# usb_snes.net
KiCad netlist of a schematic drawn in EAGLE
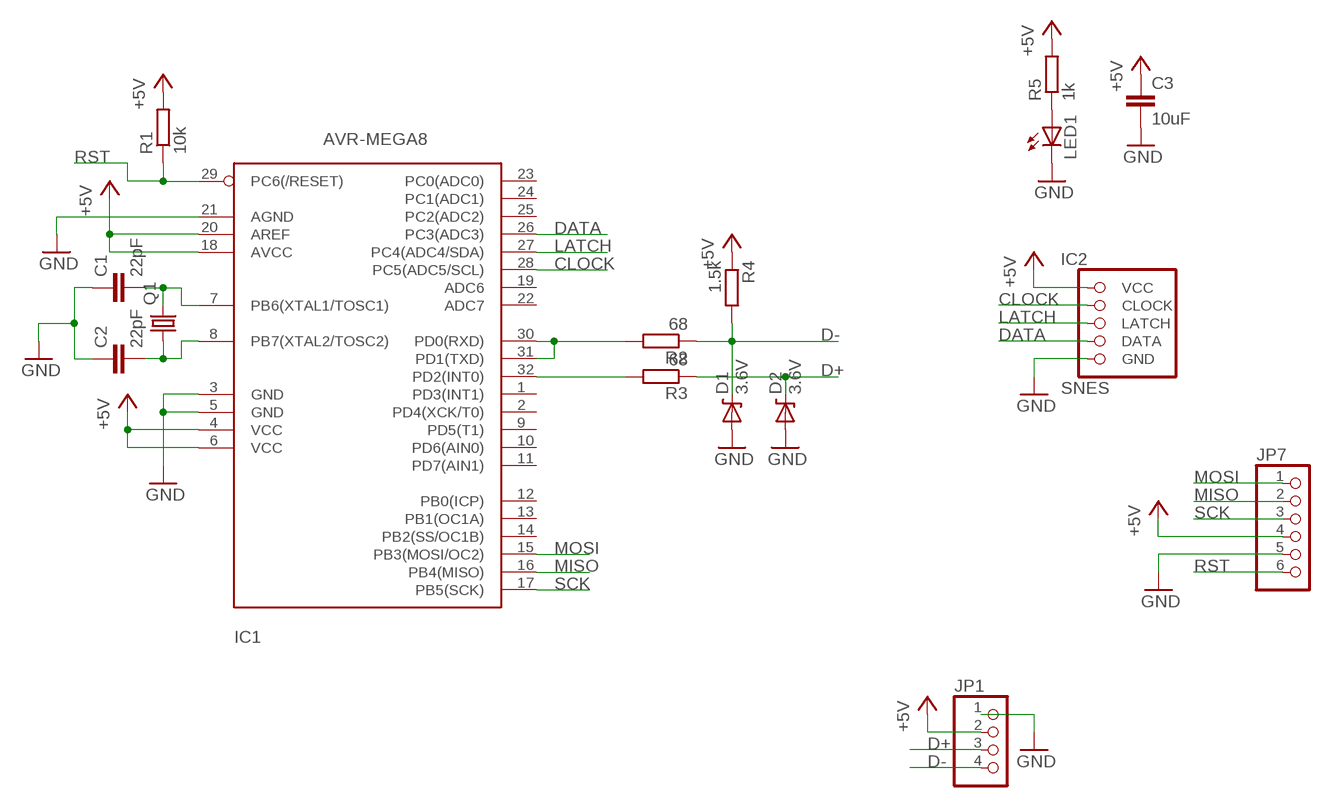
[diagram p0: schematic, sheet 1]

(export (version "E")
  (design (tool "Eeschema 10.0.6"))
  (components
    (comp (ref "C1")
      (value "22pF")
      (footprint "eagle-import:R0805")
      (libsource (lib "eagle-import") (part "C-EUR0805"))
    )
    (comp (ref "C2")
      (value "22pF")
      (footprint "eagle-import:R0805")
      (libsource (lib "eagle-import") (part "C-EUR0805"))
    )
    (comp (ref "C3")
      (value "10uF")
      (footprint "eagle-import:R0805")
      (libsource (lib "eagle-import") (part "C-EUR0805"))
    )
    (comp (ref "D1")
      (value "3.6V")
      (footprint "eagle-import:SOD123FL")
      (libsource (lib "eagle-import") (part "DIODE-ZENERFL"))
    )
    (comp (ref "D2")
      (value "3.6V")
      (footprint "eagle-import:SOD123FL")
      (libsource (lib "eagle-import") (part "DIODE-ZENERFL"))
    )
    (comp (ref "IC1")
      (value "AVR-MEGA8")
      (footprint "eagle-import:TQFP32-08")
      (libsource (lib "eagle-import") (part "AVR-MEGA8-AI"))
    )
    (comp (ref "IC2")
      (value "SNES")
      (footprint "eagle-import:SNES")
      (libsource (lib "eagle-import") (part "SNES"))
    )
    (comp (ref "JP1")
      (value "PINHD-1X4S")
      (footprint "eagle-import:1X04-2MM")
      (libsource (lib "eagle-import") (part "PINHD-1X4S"))
    )
    (comp (ref "JP7")
      (value "PINHD-1X6S")
      (footprint "eagle-import:1X06-2MM")
      (libsource (lib "eagle-import") (part "PINHD-1X6S"))
    )
    (comp (ref "LED1")
      (value "LED0805")
      (footprint "eagle-import:CHIP-LED0805")
      (libsource (lib "eagle-import") (part "LED0805"))
    )
    (comp (ref "Q1")
      (value "CRYSTALHC49UP")
      (footprint "eagle-import:HC49UP")
      (libsource (lib "eagle-import") (part "CRYSTALHC49UP"))
    )
    (comp (ref "R1")
      (value "10k")
      (footprint "eagle-import:R0805")
      (libsource (lib "eagle-import") (part "R-EU_R0805"))
    )
    (comp (ref "R2")
      (value "68")
      (footprint "eagle-import:R0805")
      (libsource (lib "eagle-import") (part "R-EU_R0805"))
    )
    (comp (ref "R3")
      (value "68")
      (footprint "eagle-import:R0805")
      (libsource (lib "eagle-import") (part "R-EU_R0805"))
    )
    (comp (ref "R4")
      (value "1.5k")
      (footprint "eagle-import:R0805")
      (libsource (lib "eagle-import") (part "R-EU_R0805"))
    )
    (comp (ref "R5")
      (value "1k")
      (footprint "eagle-import:R0805")
      (libsource (lib "eagle-import") (part "R-EU_R0805"))
    )
  )
  (nets
    (net (code "1") (name "+5V") (class "Default")
      (node (ref "C3") (pin "1") (pinfunction "1_1") (pintype "passive"))
      (node (ref "IC1") (pin "18") (pinfunction "AVCC_18") (pintype "bidirectional"))
      (node (ref "IC1") (pin "20") (pinfunction "AREF_20") (pintype "bidirectional"))
      (node (ref "IC1") (pin "4") (pinfunction "VCC_4") (pintype "bidirectional"))
      (node (ref "IC1") (pin "6") (pinfunction "VCC_6") (pintype "bidirectional"))
      (node (ref "IC2") (pin "5") (pinfunction "VCC_5") (pintype "passive"))
      (node (ref "JP1") (pin "2") (pinfunction "2_2") (pintype "passive"))
      (node (ref "JP7") (pin "4") (pinfunction "4_4") (pintype "passive"))
      (node (ref "R1") (pin "2") (pinfunction "2_2") (pintype "passive"))
      (node (ref "R4") (pin "1") (pinfunction "1_1") (pintype "passive"))
      (node (ref "R5") (pin "2") (pinfunction "2_2") (pintype "passive"))
    )
    (net (code "2") (name "/CLOCK") (class "Default")
      (node (ref "IC1") (pin "28") (pinfunction "PC5(ADC5/SCL)_28") (pintype "bidirectional"))
      (node (ref "IC2") (pin "4") (pinfunction "CLOCK_4") (pintype "passive"))
    )
    (net (code "3") (name "/D+") (class "Default")
      (node (ref "D2") (pin "C") (pinfunction "C_C") (pintype "passive"))
      (node (ref "JP1") (pin "3") (pinfunction "3_3") (pintype "passive"))
      (node (ref "R3") (pin "1") (pinfunction "1_1") (pintype "passive"))
    )
    (net (code "4") (name "/D-") (class "Default")
      (node (ref "D1") (pin "C") (pinfunction "C_C") (pintype "passive"))
      (node (ref "JP1") (pin "4") (pinfunction "4_4") (pintype "passive"))
      (node (ref "R2") (pin "1") (pinfunction "1_1") (pintype "passive"))
      (node (ref "R4") (pin "2") (pinfunction "2_2") (pintype "passive"))
    )
    (net (code "5") (name "/DATA") (class "Default")
      (node (ref "IC1") (pin "26") (pinfunction "PC3(ADC3)_26") (pintype "bidirectional"))
      (node (ref "IC2") (pin "2") (pinfunction "DATA_2") (pintype "passive"))
    )
    (net (code "6") (name "/LATCH") (class "Default")
      (node (ref "IC1") (pin "27") (pinfunction "PC4(ADC4/SDA)_27") (pintype "bidirectional"))
      (node (ref "IC2") (pin "3") (pinfunction "LATCH_3") (pintype "passive"))
    )
    (net (code "7") (name "/MISO") (class "Default")
      (node (ref "IC1") (pin "16") (pinfunction "PB4(MISO)_16") (pintype "bidirectional"))
      (node (ref "JP7") (pin "2") (pinfunction "2_2") (pintype "passive"))
    )
    (net (code "8") (name "/MOSI") (class "Default")
      (node (ref "IC1") (pin "15") (pinfunction "PB3(MOSI/OC2)_15") (pintype "bidirectional"))
      (node (ref "JP7") (pin "1") (pinfunction "1_1") (pintype "passive"))
    )
    (net (code "9") (name "/RST") (class "Default")
      (node (ref "IC1") (pin "29") (pinfunction "PC6(/RESET)_29") (pintype "bidirectional"))
      (node (ref "JP7") (pin "6") (pinfunction "6_6") (pintype "passive"))
      (node (ref "R1") (pin "1") (pinfunction "1_1") (pintype "passive"))
    )
    (net (code "10") (name "/SCK") (class "Default")
      (node (ref "IC1") (pin "17") (pinfunction "PB5(SCK)_17") (pintype "bidirectional"))
      (node (ref "JP7") (pin "3") (pinfunction "3_3") (pintype "passive"))
    )
    (net (code "11") (name "GND") (class "Default")
      (node (ref "C1") (pin "1") (pinfunction "1_1") (pintype "passive"))
      (node (ref "C2") (pin "1") (pinfunction "1_1") (pintype "passive"))
      (node (ref "C3") (pin "2") (pinfunction "2_2") (pintype "passive"))
      (node (ref "D1") (pin "A") (pinfunction "A_A") (pintype "passive"))
      (node (ref "D2") (pin "A") (pinfunction "A_A") (pintype "passive"))
      (node (ref "IC1") (pin "21") (pinfunction "AGND_21") (pintype "bidirectional"))
      (node (ref "IC1") (pin "3") (pinfunction "GND_3") (pintype "bidirectional"))
      (node (ref "IC1") (pin "5") (pinfunction "GND_5") (pintype "bidirectional"))
      (node (ref "IC2") (pin "1") (pinfunction "GND_1") (pintype "passive"))
      (node (ref "JP1") (pin "1") (pinfunction "1_1") (pintype "passive"))
      (node (ref "JP7") (pin "5") (pinfunction "5_5") (pintype "passive"))
      (node (ref "LED1") (pin "C") (pinfunction "C_C") (pintype "passive"))
    )
    (net (code "12") (name "Net-(IC1-PB6(XTAL1{slash}TOSC1))") (class "Default")
      (node (ref "C1") (pin "2") (pinfunction "2_2") (pintype "passive"))
      (node (ref "IC1") (pin "7") (pinfunction "PB6(XTAL1/TOSC1)_7") (pintype "bidirectional"))
      (node (ref "Q1") (pin "2") (pinfunction "2_2") (pintype "passive"))
    )
    (net (code "13") (name "Net-(IC1-PB7(XTAL2{slash}TOSC2))") (class "Default")
      (node (ref "C2") (pin "2") (pinfunction "2_2") (pintype "passive"))
      (node (ref "IC1") (pin "8") (pinfunction "PB7(XTAL2/TOSC2)_8") (pintype "bidirectional"))
      (node (ref "Q1") (pin "1") (pinfunction "1_1") (pintype "passive"))
    )
    (net (code "14") (name "Net-(IC1-PD0(RXD))") (class "Default")
      (node (ref "IC1") (pin "30") (pinfunction "PD0(RXD)_30") (pintype "bidirectional"))
      (node (ref "IC1") (pin "31") (pinfunction "PD1(TXD)_31") (pintype "bidirectional"))
      (node (ref "R2") (pin "2") (pinfunction "2_2") (pintype "passive"))
    )
    (net (code "15") (name "Net-(IC1-PD2(INT0))") (class "Default")
      (node (ref "IC1") (pin "32") (pinfunction "PD2(INT0)_32") (pintype "bidirectional"))
      (node (ref "R3") (pin "2") (pinfunction "2_2") (pintype "passive"))
    )
    (net (code "16") (name "Net-(LED1-PadA)") (class "Default")
      (node (ref "LED1") (pin "A") (pinfunction "A_A") (pintype "passive"))
      (node (ref "R5") (pin "1") (pinfunction "1_1") (pintype "passive"))
    )
    (net (code "17") (name "unconnected-(IC1-ADC6-Pad19)") (class "Default")
      (node (ref "IC1") (pin "19") (pinfunction "ADC6_19") (pintype "bidirectional"))
    )
    (net (code "18") (name "unconnected-(IC1-ADC7-Pad22)") (class "Default")
      (node (ref "IC1") (pin "22") (pinfunction "ADC7_22") (pintype "bidirectional"))
    )
    (net (code "19") (name "unconnected-(IC1-PB0(ICP)-Pad12)") (class "Default")
      (node (ref "IC1") (pin "12") (pinfunction "PB0(ICP)_12") (pintype "bidirectional"))
    )
    (net (code "20") (name "unconnected-(IC1-PB1(OC1A)-Pad13)") (class "Default")
      (node (ref "IC1") (pin "13") (pinfunction "PB1(OC1A)_13") (pintype "bidirectional"))
    )
    (net (code "21") (name "unconnected-(IC1-PB2(SS{slash}OC1B)-Pad14)") (class "Default")
      (node (ref "IC1") (pin "14") (pinfunction "PB2(SS/OC1B)_14") (pintype "bidirectional"))
    )
    (net (code "22") (name "unconnected-(IC1-PC0(ADC0)-Pad23)") (class "Default")
      (node (ref "IC1") (pin "23") (pinfunction "PC0(ADC0)_23") (pintype "bidirectional"))
    )
    (net (code "23") (name "unconnected-(IC1-PC1(ADC1)-Pad24)") (class "Default")
      (node (ref "IC1") (pin "24") (pinfunction "PC1(ADC1)_24") (pintype "bidirectional"))
    )
    (net (code "24") (name "unconnected-(IC1-PC2(ADC2)-Pad25)") (class "Default")
      (node (ref "IC1") (pin "25") (pinfunction "PC2(ADC2)_25") (pintype "bidirectional"))
    )
    (net (code "25") (name "unconnected-(IC1-PD3(INT1)-Pad1)") (class "Default")
      (node (ref "IC1") (pin "1") (pinfunction "PD3(INT1)_1") (pintype "bidirectional"))
    )
    (net (code "26") (name "unconnected-(IC1-PD4(XCK{slash}T0)-Pad2)") (class "Default")
      (node (ref "IC1") (pin "2") (pinfunction "PD4(XCK/T0)_2") (pintype "bidirectional"))
    )
    (net (code "27") (name "unconnected-(IC1-PD5(T1)-Pad9)") (class "Default")
      (node (ref "IC1") (pin "9") (pinfunction "PD5(T1)_9") (pintype "bidirectional"))
    )
    (net (code "28") (name "unconnected-(IC1-PD6(AIN0)-Pad10)") (class "Default")
      (node (ref "IC1") (pin "10") (pinfunction "PD6(AIN0)_10") (pintype "bidirectional"))
    )
    (net (code "29") (name "unconnected-(IC1-PD7(AIN1)-Pad11)") (class "Default")
      (node (ref "IC1") (pin "11") (pinfunction "PD7(AIN1)_11") (pintype "bidirectional"))
    )
  )
)
